# BatteryCharger.net
KiCad netlist of a schematic drawn in Altium Designer
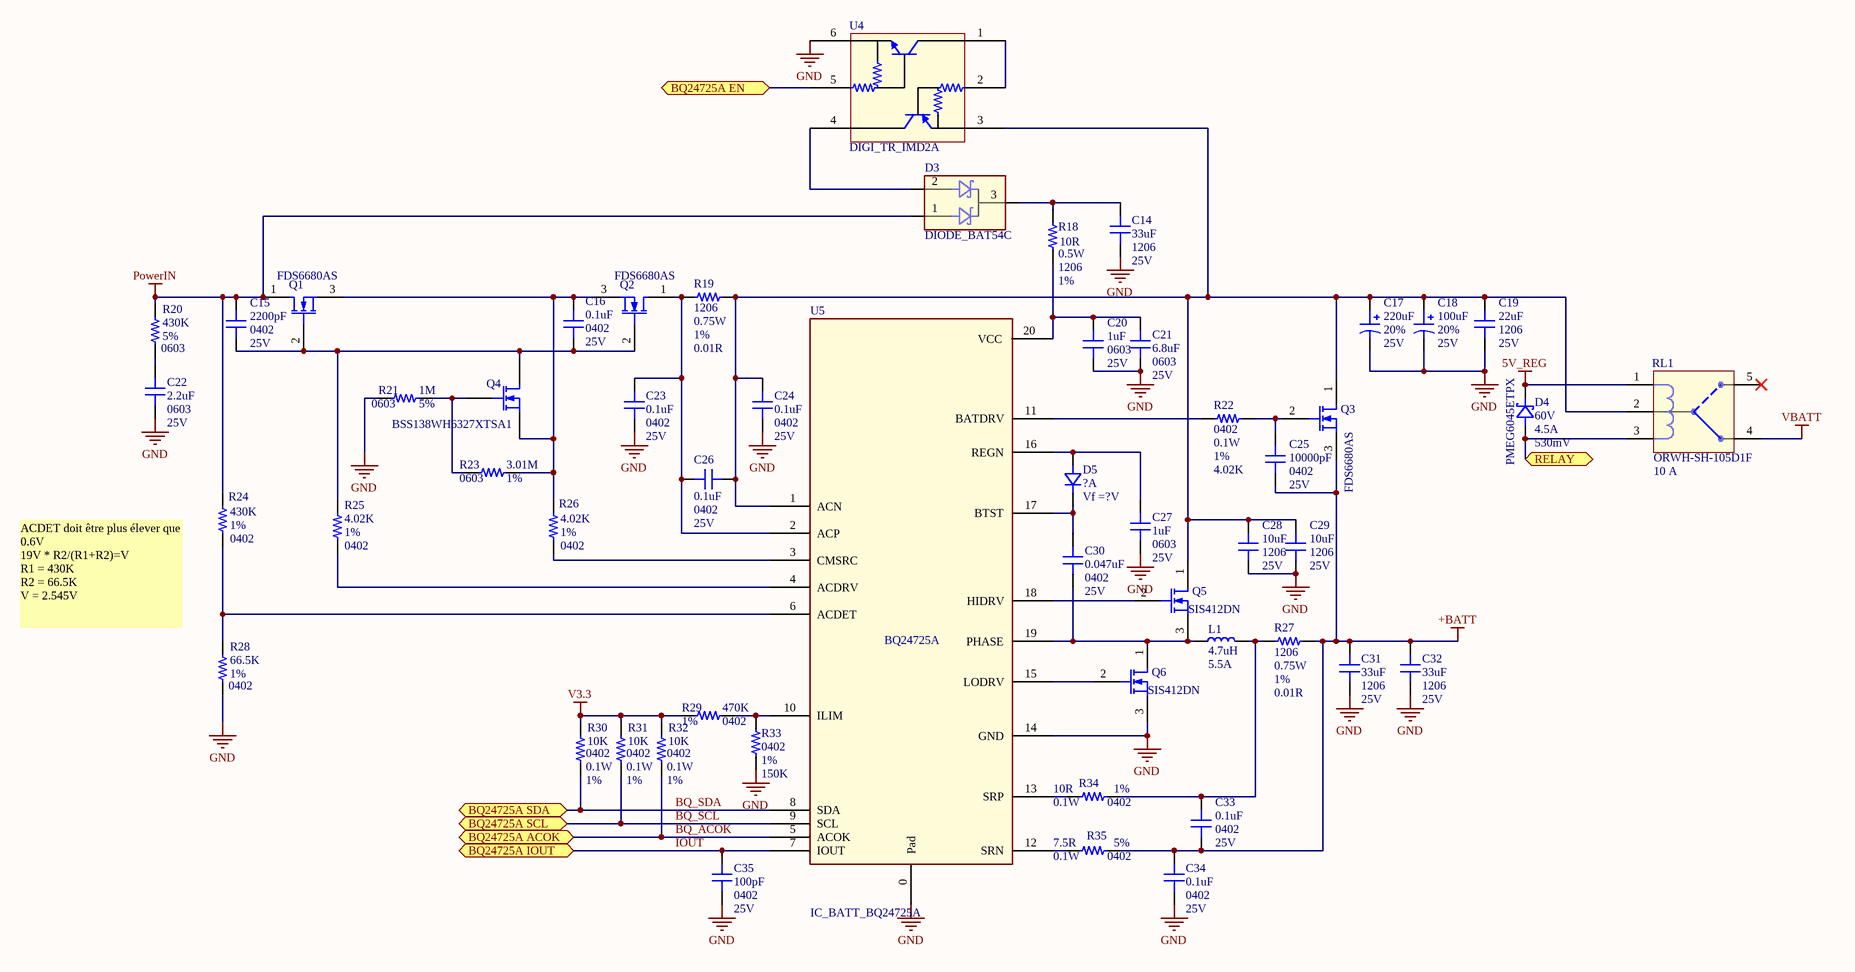
[diagram p0: BatteryCharger.SchDoc]

(export (version "E")
  (design (tool "Eeschema 10.0.6"))
  (components
    (comp (ref "C14")
      (value "33uF")
      (footprint "CAP_1206")
      (description "CAP CER 33uF 25V 1206")
      (fields
        (field (name "PART NUMBER") "C3216JB1E336M160AC‎")
        (field (name "PACKAGE") "1206")
        (field (name "VOLTAGE") "25V")
        (field (name "Comment") "CAP_‎C3216JB1E336M160AC‎")
      )
      (libsource (lib "SecureBot") (part "CAP_‎C3216JB1E336M160AC‎"))
    )
    (comp (ref "C15")
      (value "2200pF")
      (footprint "CAP_0402")
      (description "CAP CER 2200PF 25V 0402")
      (fields
        (field (name "PART NUMBER") "AC0402KRX7R8BB222‎")
        (field (name "PACKAGE") "0402")
        (field (name "VOLTAGE") "25V")
        (field (name "Comment") "CAP_AC0402KRX7R8BB222‎")
      )
      (libsource (lib "SecureBot") (part "CAP_AC0402KRX7R8BB222‎"))
    )
    (comp (ref "C16")
      (value "0.1uF")
      (footprint "CAP_0402")
      (description "CAP CER 0.1uF 25V 0402")
      (fields
        (field (name "PART NUMBER") "CL05A104KA5NNNC‎")
        (field (name "PACKAGE") "0402")
        (field (name "VOLTAGE") "25V")
        (field (name "Comment") "CAP_‎‎CL05A104KA5NNNC‎")
      )
      (libsource (lib "SecureBot") (part "CAP_‎‎CL05A104KA5NNNC‎"))
    )
    (comp (ref "C17")
      (value "220uF")
      (footprint "CAP UWT 8x10")
      (description "CAP ALU 220µF 25V")
      (fields
        (field (name "PART NUMBER") "UWT1E221MNL1GS")
        (field (name "TOLERANCE") "20%")
        (field (name "VOLTAGE") "25V")
        (field (name "Comment") "CAP_UWT1E221MNL1GS")
      )
      (libsource (lib "SecureBot") (part "CAP_UWT1E221MNL1GS"))
    )
    (comp (ref "C18")
      (value "100uF")
      (footprint "CAP ALU - 6.3mm DIA")
      (description "CAP ALU 100µF 25V")
      (fields
        (field (name "PART NUMBER") "UWT1E101MCL1GS")
        (field (name "TOLERANCE") "20%")
        (field (name "VOLTAGE") "25V")
        (field (name "Comment") "CAP_UWT1E101MCL1GS")
      )
      (libsource (lib "SecureBot") (part "CAP_UWT1E101MCL1GS"))
    )
    (comp (ref "C19")
      (value "22uF")
      (footprint "CAP_1206")
      (description "CAP CER 22uF 25V 1206")
      (fields
        (field (name "PART NUMBER") "CL31A226KAHNNNE‎")
        (field (name "PACKAGE") "1206")
        (field (name "VOLTAGE") "25V")
        (field (name "Comment") "CAP_‎‎CL31A226KAHNNNE‎")
      )
      (libsource (lib "SecureBot") (part "CAP_‎‎CL31A226KAHNNNE‎"))
    )
    (comp (ref "C20")
      (value "1uF")
      (footprint "CAP_0603")
      (description "CAP CER 1uF 25V 0603")
      (fields
        (field (name "PART NUMBER") "CL10A105KA8NNNC‎")
        (field (name "PACKAGE") "0603")
        (field (name "VOLTAGE") "25V")
        (field (name "Comment") "CAP_‎CL10A105KA8NNNC‎")
      )
      (libsource (lib "SecureBot") (part "CAP_‎CL10A105KA8NNNC‎"))
    )
    (comp (ref "C21")
      (value "6.8uF")
      (footprint "CAP_0603")
      (description "CAP CER 6.8uF 25V 0603")
      (fields
        (field (name "PART NUMBER") "C1608X5R1E685K080AC")
        (field (name "PACKAGE") "0603")
        (field (name "VOLTAGE") "25V")
        (field (name "Comment") "CAP_‎‎‎C1608X5R1E685K080AC")
      )
      (libsource (lib "SecureBot") (part "CAP_‎‎‎C1608X5R1E685K080AC"))
    )
    (comp (ref "C22")
      (value "2.2uF")
      (footprint "CAP_0603")
      (description "CAP CER 2.2uF 25V 0603")
      (fields
        (field (name "PART NUMBER") "GRM188R61E225KA12D‎")
        (field (name "PACKAGE") "0603")
        (field (name "VOLTAGE") "25V")
        (field (name "Comment") "CAP_‎‎GRM188R61E225KA12D‎")
      )
      (libsource (lib "SecureBot") (part "CAP_‎‎GRM188R61E225KA12D‎"))
    )
    (comp (ref "C23")
      (value "0.1uF")
      (footprint "CAP_0402")
      (description "CAP CER 0.1uF 25V 0402")
      (fields
        (field (name "PART NUMBER") "CL05A104KA5NNNC‎")
        (field (name "PACKAGE") "0402")
        (field (name "VOLTAGE") "25V")
        (field (name "Comment") "CAP_‎‎CL05A104KA5NNNC‎")
      )
      (libsource (lib "SecureBot") (part "CAP_‎‎CL05A104KA5NNNC‎"))
    )
    (comp (ref "C24")
      (value "0.1uF")
      (footprint "CAP_0402")
      (description "CAP CER 0.1uF 25V 0402")
      (fields
        (field (name "PART NUMBER") "CL05A104KA5NNNC‎")
        (field (name "PACKAGE") "0402")
        (field (name "VOLTAGE") "25V")
        (field (name "Comment") "CAP_‎‎CL05A104KA5NNNC‎")
      )
      (libsource (lib "SecureBot") (part "CAP_‎‎CL05A104KA5NNNC‎"))
    )
    (comp (ref "C25")
      (value "10000pF")
      (footprint "CAP_0402")
      (description "CAP CER 10000pF 25V 0402")
      (fields
        (field (name "PART NUMBER") "‎CL05B103KA5NNNC‎")
        (field (name "PACKAGE") "0402")
        (field (name "VOLTAGE") "25V")
        (field (name "Comment") "CAP_‎CL05B103KA5NNNC‎")
      )
      (libsource (lib "SecureBot") (part "CAP_‎CL05B103KA5NNNC‎"))
    )
    (comp (ref "C26")
      (value "0.1uF")
      (footprint "CAP_0402")
      (description "CAP CER 0.1uF 25V 0402")
      (fields
        (field (name "PART NUMBER") "CL05A104KA5NNNC‎")
        (field (name "PACKAGE") "0402")
        (field (name "VOLTAGE") "25V")
        (field (name "Comment") "CAP_‎‎CL05A104KA5NNNC‎")
      )
      (libsource (lib "SecureBot") (part "CAP_‎‎CL05A104KA5NNNC‎"))
    )
    (comp (ref "C27")
      (value "1uF")
      (footprint "CAP_0603")
      (description "CAP CER 1uF 25V 0603")
      (fields
        (field (name "PART NUMBER") "CL10A105KA8NNNC‎")
        (field (name "PACKAGE") "0603")
        (field (name "VOLTAGE") "25V")
        (field (name "Comment") "CAP_‎CL10A105KA8NNNC‎")
      )
      (libsource (lib "SecureBot") (part "CAP_‎CL10A105KA8NNNC‎"))
    )
    (comp (ref "C28")
      (value "10uF")
      (footprint "CAP_1206")
      (description "CAP CER 10uF 25V 1206")
      (fields
        (field (name "PART NUMBER") "CL31A106KAHNFNE‎")
        (field (name "PACKAGE") "1206")
        (field (name "VOLTAGE") "25V")
        (field (name "Comment") "CAP_‎CL31A106KAHNFNE‎")
      )
      (libsource (lib "SecureBot") (part "CAP_‎CL31A106KAHNFNE‎"))
    )
    (comp (ref "C29")
      (value "10uF")
      (footprint "CAP_1206")
      (description "CAP CER 10uF 25V 1206")
      (fields
        (field (name "PART NUMBER") "CL31A106KAHNFNE‎")
        (field (name "PACKAGE") "1206")
        (field (name "VOLTAGE") "25V")
        (field (name "Comment") "CAP_‎CL31A106KAHNFNE‎")
      )
      (libsource (lib "SecureBot") (part "CAP_‎CL31A106KAHNFNE‎"))
    )
    (comp (ref "C30")
      (value "0.047uF")
      (footprint "CAP_0402")
      (description "CAP CER 0.047uF 25V 0402")
      (fields
        (field (name "PART NUMBER") "‎C0402C473K3RACAUTO‎")
        (field (name "PACKAGE") "0402")
        (field (name "VOLTAGE") "25V")
        (field (name "Comment") "CAP_‎‎‎C0402C473K3RACAUTO‎")
      )
      (libsource (lib "SecureBot") (part "CAP_‎‎‎C0402C473K3RACAUTO‎"))
    )
    (comp (ref "C31")
      (value "33uF")
      (footprint "CAP_1206")
      (description "CAP CER 33uF 25V 1206")
      (fields
        (field (name "PART NUMBER") "C3216JB1E336M160AC‎")
        (field (name "PACKAGE") "1206")
        (field (name "VOLTAGE") "25V")
        (field (name "Comment") "CAP_‎C3216JB1E336M160AC‎")
      )
      (libsource (lib "SecureBot") (part "CAP_‎C3216JB1E336M160AC‎"))
    )
    (comp (ref "C32")
      (value "33uF")
      (footprint "CAP_1206")
      (description "CAP CER 33uF 25V 1206")
      (fields
        (field (name "PART NUMBER") "C3216JB1E336M160AC‎")
        (field (name "PACKAGE") "1206")
        (field (name "VOLTAGE") "25V")
        (field (name "Comment") "CAP_‎C3216JB1E336M160AC‎")
      )
      (libsource (lib "SecureBot") (part "CAP_‎C3216JB1E336M160AC‎"))
    )
    (comp (ref "C33")
      (value "0.1uF")
      (footprint "CAP_0402")
      (description "CAP CER 0.1uF 25V 0402")
      (fields
        (field (name "PART NUMBER") "CL05A104KA5NNNC‎")
        (field (name "PACKAGE") "0402")
        (field (name "VOLTAGE") "25V")
        (field (name "Comment") "CAP_‎‎CL05A104KA5NNNC‎")
      )
      (libsource (lib "SecureBot") (part "CAP_‎‎CL05A104KA5NNNC‎"))
    )
    (comp (ref "C34")
      (value "0.1uF")
      (footprint "CAP_0402")
      (description "CAP CER 0.1uF 25V 0402")
      (fields
        (field (name "PART NUMBER") "CL05A104KA5NNNC‎")
        (field (name "PACKAGE") "0402")
        (field (name "VOLTAGE") "25V")
        (field (name "Comment") "CAP_‎‎CL05A104KA5NNNC‎")
      )
      (libsource (lib "SecureBot") (part "CAP_‎‎CL05A104KA5NNNC‎"))
    )
    (comp (ref "C35")
      (value "100pF")
      (footprint "CAP_0402")
      (description "CAP CER 100pF 25V 0402")
      (fields
        (field (name "PART NUMBER") "CC0402KRX7R8BB101‎")
        (field (name "PACKAGE") "0402")
        (field (name "VOLTAGE") "25V")
        (field (name "Comment") "CAP_‎‎‎‎CC0402KRX7R8BB101‎")
      )
      (libsource (lib "SecureBot") (part "CAP_‎‎‎‎CC0402KRX7R8BB101‎"))
    )
    (comp (ref "D3")
      (value "DIODE_BAT54C")
      (footprint "BAT54C")
      (description "Dual input Diode")
      (fields (field (name "PART NUMBER") "BAT54C"))
      (libsource (lib "SecureBot") (part "DIODE_BAT54C"))
    )
    (comp (ref "D4")
      (value "DIODE_SCH_PMEG6045ETPX")
      (footprint "DO-214AC_SOD128")
      (description "Diode Schottky 60V 4.5A Surface Mount CFP5")
      (fields
        (field (name "VOLTAGE") "60V")
        (field (name "CURRENT") "4.5A")
        (field (name "VF") "530mV")
        (field (name "PART NUMBER") "PMEG6045ETPX")
      )
      (libsource (lib "SecureBot") (part "DIODE_SCH_PMEG6045ETPX"))
    )
    (comp (ref "D5")
      (value "DIODE BAT54")
      (footprint "BAT54")
      (fields
        (field (name "CURRENT") "?A")
        (field (name "VF") "Vf =?V")
        (field (name "PART NUMBER") "BAT54C")
      )
      (libsource (lib "SecureBot") (part "DIODE BAT54"))
    )
    (comp (ref "L1")
      (value "4.7uH")
      (footprint "ASPI-0630LR")
      (description "4.7µH Shielded Molded Inductor 5.5A 35mOhm")
      (fields
        (field (name "CURRENT") "5.5A")
        (field (name "PART NUMBER") "ASPI-0630LR")
        (field (name "Comment") "IND_ASPI-0630LR")
      )
      (libsource (lib "SecureBot") (part "IND_ASPI-0630LR"))
    )
    (comp (ref "Q1")
      (value "NMOS_FDS6680AS")
      (footprint "SO-8 FDS6680AS")
      (description "NMOS_N-Channel 30V 11.5A (Ta) 2.5W (Ta) Surface Mount 8-SOIC")
      (fields (field (name "PART NUMBER") "FDS6680AS"))
      (libsource (lib "SecureBot") (part "NMOS_FDS6680AS"))
    )
    (comp (ref "Q2")
      (value "NMOS_FDS6680AS")
      (footprint "SO-8 FDS6680AS")
      (description "NMOS_N-Channel 30V 11.5A (Ta) 2.5W (Ta) Surface Mount 8-SOIC")
      (fields (field (name "PART NUMBER") "FDS6680AS"))
      (libsource (lib "SecureBot") (part "NMOS_FDS6680AS"))
    )
    (comp (ref "Q3")
      (value "NMOS_FDS6680AS")
      (footprint "SO-8 FDS6680AS")
      (description "NMOS_N-Channel 30V 11.5A (Ta) 2.5W (Ta) Surface Mount 8-SOIC")
      (fields (field (name "PART NUMBER") "FDS6680AS"))
      (libsource (lib "SecureBot") (part "NMOS_FDS6680AS"))
    )
    (comp (ref "Q4")
      (value "MOSFET-N")
      (footprint "PG-SOT-323")
      (description "N-Channel MOSFET")
      (fields (field (name "PART NUMBER") "BSS138WH6327XTSA1") (field (name "PUBLISHER") "Altium Limited"))
      (libsource (lib "Miscellaneous Devices") (part "MOSFET-N"))
    )
    (comp (ref "Q5")
      (value "NMOS_SIS412DN")
      (footprint "SiS412DN")
      (description "NMOS_N-Channel 30V 12A (Tc) 3.2W (Ta), 15.6W (Tc)")
      (fields (field (name "PART NUMBER") "SIS412DN"))
      (libsource (lib "SecureBot") (part "NMOS_SIS412DN"))
    )
    (comp (ref "Q6")
      (value "NMOS_SIS412DN")
      (footprint "SiS412DN")
      (description "NMOS_N-Channel 30V 12A (Tc) 3.2W (Ta), 15.6W (Tc)")
      (fields (field (name "PART NUMBER") "SIS412DN"))
      (libsource (lib "SecureBot") (part "NMOS_SIS412DN"))
    )
    (comp (ref "R18")
      (value "10R")
      (footprint "RES_1206")
      (description "RES 10R 1% 1/2W 1206")
      (fields
        (field (name "PART NUMBER") "CRM1206-FX-10R0ELF‎")
        (field (name "POWER") "0.5W")
        (field (name "PACKAGE") "1206")
        (field (name "TOLERANCE") "1%")
        (field (name "Comment") "RES_CRM1206-FX-10R0ELF‎")
      )
      (libsource (lib "SecureBot") (part "RES_CRM1206-FX-10R0ELF‎"))
    )
    (comp (ref "R19")
      (value "0.01R")
      (footprint "RES_1206")
      (description "RES 0.01R 1% 3/4W 1206")
      (fields
        (field (name "PART NUMBER") "KRL1632E-M-R010-F-T5")
        (field (name "PACKAGE") "1206")
        (field (name "POWER") "0.75W")
        (field (name "TOLERANCE") "1%")
        (field (name "Comment") "RES_‎‎‎KRL1632E-M-R010-F-T5")
      )
      (libsource (lib "SecureBot") (part "RES_‎‎‎KRL1632E-M-R010-F-T5"))
    )
    (comp (ref "R20")
      (value "430K")
      (footprint "RES_0603")
      (description "RES 430K 5% 1/10W 0603")
      (fields
        (field (name "PART NUMBER") "RC0603JR-07430KL‎")
        (field (name "PACKAGE") "0603")
        (field (name "POWER") "0.1W")
        (field (name "TOLERANCE") "5%")
      )
      (libsource (lib "SecureBot") (part "RES_‎‎‎‎RC0603JR-07430KL‎"))
    )
    (comp (ref "R21")
      (value "1M")
      (footprint "RES_0603")
      (description "RES 1M 5% 1/10W 0603")
      (fields
        (field (name "PART NUMBER") "‎ERA-6AEB4020V‎")
        (field (name "PACKAGE") "0603")
        (field (name "POWER") "0.1W")
        (field (name "TOLERANCE") "5%")
      )
      (libsource (lib "SecureBot") (part "RES_‎‎‎ERA-6AEB4020V‎_1"))
    )
    (comp (ref "R22")
      (value "4.02K")
      (footprint "RES_0402")
      (description "RES 4.02K 1% 1/10W 0402")
      (fields
        (field (name "PART NUMBER") "ERJ-2RKF4021X‎")
        (field (name "PACKAGE") "0402")
        (field (name "POWER") "0.1W")
        (field (name "TOLERANCE") "1%")
        (field (name "Comment") "RES_‎‎‎ERJ-2RKF4021X‎")
      )
      (libsource (lib "SecureBot") (part "RES_‎‎‎ERJ-2RKF4021X‎"))
    )
    (comp (ref "R23")
      (value "3.01M")
      (footprint "RES_0603")
      (description "RES 3.01M 1% 1/10W 0603")
      (fields
        (field (name "PART NUMBER") "RC0603FR-073M01L‎")
        (field (name "PACKAGE") "0603")
        (field (name "POWER") "0.1W")
        (field (name "TOLERANCE") "1%")
      )
      (libsource (lib "SecureBot") (part "RES_‎‎‎‎RC0603FR-073M01L‎"))
    )
    (comp (ref "R24")
      (value "430K")
      (footprint "RES_0402")
      (description "RES 430K 1% 1/16W 0402")
      (fields
        (field (name "PART NUMBER") "RC0402FR-07430KL‎")
        (field (name "PACKAGE") "0402")
        (field (name "POWER") "0.0625W")
        (field (name "TOLERANCE") "1%")
      )
      (libsource (lib "SecureBot") (part "RES_RC0402FR-07430KL‎"))
    )
    (comp (ref "R25")
      (value "4.02K")
      (footprint "RES_0402")
      (description "RES 4.02K 1% 1/10W 0402")
      (fields
        (field (name "PART NUMBER") "ERJ-2RKF4021X‎")
        (field (name "PACKAGE") "0402")
        (field (name "POWER") "0.1W")
        (field (name "TOLERANCE") "1%")
      )
      (libsource (lib "SecureBot") (part "RES_‎‎‎ERJ-2RKF4021X‎"))
    )
    (comp (ref "R26")
      (value "4.02K")
      (footprint "RES_0402")
      (description "RES 4.02K 1% 1/10W 0402")
      (fields
        (field (name "PART NUMBER") "ERJ-2RKF4021X‎")
        (field (name "PACKAGE") "0402")
        (field (name "POWER") "0.1W")
        (field (name "TOLERANCE") "1%")
      )
      (libsource (lib "SecureBot") (part "RES_‎‎‎ERJ-2RKF4021X‎"))
    )
    (comp (ref "R27")
      (value "0.01R")
      (footprint "RES_1206")
      (description "RES 0.01R 1% 3/4W 1206")
      (fields
        (field (name "PART NUMBER") "KRL1632E-M-R010-F-T5")
        (field (name "PACKAGE") "1206")
        (field (name "POWER") "0.75W")
        (field (name "TOLERANCE") "1%")
        (field (name "Comment") "RES_‎‎‎KRL1632E-M-R010-F-T5")
      )
      (libsource (lib "SecureBot") (part "RES_‎‎‎KRL1632E-M-R010-F-T5"))
    )
    (comp (ref "R28")
      (value "66.5K")
      (footprint "RES_0402")
      (description "RES 66.5K 1% 1/16W 0402")
      (fields
        (field (name "PART NUMBER") "RMCF0402FT66K5")
        (field (name "PACKAGE") "0402")
        (field (name "POWER") "0.0625W")
        (field (name "TOLERANCE") "1%")
      )
      (libsource (lib "SecureBot") (part "RES_‎‎‎‎RMCF0402FT66K5"))
    )
    (comp (ref "R29")
      (value "470K")
      (footprint "RES_0402")
      (description "RES 470K 1% 1/10W 0402")
      (fields
        (field (name "PART NUMBER") "MCS04020C4703FE000‎")
        (field (name "PACKAGE") "0402")
        (field (name "POWER") "0.1W")
        (field (name "TOLERANCE") "1%")
      )
      (libsource (lib "SecureBot") (part "RES_MCS04020C4703FE000‎"))
    )
    (comp (ref "R30")
      (value "10K")
      (footprint "RES_0402")
      (description "RES 10K 1% 1/10W 0402")
      (fields
        (field (name "PART NUMBER") "‎MCS0402MC1002FE000‎")
        (field (name "PACKAGE") "0402")
        (field (name "POWER") "0.1W")
        (field (name "TOLERANCE") "1%")
        (field (name "Comment") "RES_‎MCS0402MC1002FE000‎")
      )
      (libsource (lib "SecureBot") (part "RES_‎MCS0402MC1002FE000‎"))
    )
    (comp (ref "R31")
      (value "10K")
      (footprint "RES_0402")
      (description "RES 10K 1% 1/10W 0402")
      (fields
        (field (name "PART NUMBER") "‎MCS0402MC1002FE000‎")
        (field (name "PACKAGE") "0402")
        (field (name "POWER") "0.1W")
        (field (name "TOLERANCE") "1%")
        (field (name "Comment") "RES_‎MCS0402MC1002FE000‎")
      )
      (libsource (lib "SecureBot") (part "RES_‎MCS0402MC1002FE000‎"))
    )
    (comp (ref "R32")
      (value "10K")
      (footprint "RES_0402")
      (description "RES 10K 1% 1/10W 0402")
      (fields
        (field (name "PART NUMBER") "‎MCS0402MC1002FE000‎")
        (field (name "PACKAGE") "0402")
        (field (name "POWER") "0.1W")
        (field (name "TOLERANCE") "1%")
        (field (name "Comment") "RES_‎MCS0402MC1002FE000‎")
      )
      (libsource (lib "SecureBot") (part "RES_‎MCS0402MC1002FE000‎"))
    )
    (comp (ref "R33")
      (value "150K")
      (footprint "RES_0402")
      (description "RES 150K 1% 1/10W 0402")
      (fields
        (field (name "PART NUMBER") "MCS04020C1503FE000‎")
        (field (name "PACKAGE") "0402")
        (field (name "POWER") "0.1W")
        (field (name "TOLERANCE") "1%")
      )
      (libsource (lib "SecureBot") (part "RES_‎‎‎MCS04020C1503FE000‎"))
    )
    (comp (ref "R34")
      (value "10R")
      (footprint "RES_0402")
      (description "RES 10R 1% 1/10W 0402")
      (fields
        (field (name "PART NUMBER") "ERJ-2RKF10R0X‎")
        (field (name "POWER") "0.1W")
        (field (name "TOLERANCE") "1%")
        (field (name "PACKAGE") "0402")
        (field (name "Comment") "RES_ERJ-2RKF10R0X‎")
      )
      (libsource (lib "SecureBot") (part "RES_ERJ-2RKF10R0X‎"))
    )
    (comp (ref "R35")
      (value "7.5R")
      (footprint "RES_0402")
      (description "RES 7.5R 5% 1/10W 0402")
      (fields
        (field (name "PART NUMBER") "ERJ-2GEJ7R5X‎")
        (field (name "PACKAGE") "0402")
        (field (name "POWER") "0.1W")
        (field (name "TOLERANCE") "5%")
        (field (name "Comment") "RES_‎‎‎ERJ-2GEJ7R5X‎")
      )
      (libsource (lib "SecureBot") (part "RES_‎‎‎ERJ-2GEJ7R5X‎"))
    )
    (comp (ref "RL1")
      (value "Relay SPDT")
      (footprint "ORWH-SH")
      (fields (field (name "PART NUMBER") "ORWH-SH-105D1F") (field (name "A MAX") "10 A"))
      (libsource (lib "SecureBot") (part "Relay SPDT"))
    )
    (comp (ref "U4")
      (value "DIGI_TR_IMD2A")
      (footprint "IMD2A")
      (description "Dual digital Transistor")
      (fields (field (name "PART NUMBER") "IMD2A"))
      (libsource (lib "SecureBot") (part "DIGI_TR_IMD2A"))
    )
    (comp (ref "U5")
      (value "IC_BATT_BQ24725A")
      (footprint "bq24725A")
      (description "Battery Charger")
      (fields (field (name "PART NUMBER") "BQ24725A"))
      (libsource (lib "SecureBot") (part "IC_BATT_BQ24725A"))
    )
  )
  (nets
    (net (code "1") (name "+BATT") (class "Default")
      (node (ref "C25") (pin "2") (pinfunction "2_2") (pintype "passive"))
      (node (ref "C31") (pin "1") (pinfunction "1_1") (pintype "passive"))
      (node (ref "C32") (pin "1") (pinfunction "1_1") (pintype "passive"))
      (node (ref "C33") (pin "2") (pinfunction "2_2") (pintype "passive"))
      (node (ref "C34") (pin "1") (pinfunction "1_1") (pintype "passive"))
      (node (ref "Q3") (pin "3") (pinfunction "S_3") (pintype "passive"))
      (node (ref "R27") (pin "2") (pinfunction "2_2") (pintype "passive"))
      (node (ref "R35") (pin "2") (pinfunction "2_2") (pintype "passive"))
    )
    (net (code "2") (name "/BQ24725A EN") (class "Default")
      (node (ref "U4") (pin "5") (pinfunction "5_5") (pintype "passive"))
    )
    (net (code "3") (name "/BQ_ACOK") (class "Default")
      (node (ref "R32") (pin "2") (pinfunction "2_2") (pintype "passive"))
      (node (ref "U5") (pin "5") (pinfunction "ACOK_5") (pintype "passive"))
    )
    (net (code "4") (name "/BQ_SCL") (class "Default")
      (node (ref "R31") (pin "2") (pinfunction "2_2") (pintype "passive"))
      (node (ref "U5") (pin "9") (pinfunction "SCL_9") (pintype "passive"))
    )
    (net (code "5") (name "/BQ_SDA") (class "Default")
      (node (ref "R30") (pin "2") (pinfunction "2_2") (pintype "passive"))
      (node (ref "U5") (pin "8") (pinfunction "SDA_8") (pintype "passive"))
    )
    (net (code "6") (name "/IOUT") (class "Default")
      (node (ref "C35") (pin "1") (pinfunction "1_1") (pintype "passive"))
      (node (ref "U5") (pin "7") (pinfunction "IOUT_7") (pintype "passive"))
    )
    (net (code "7") (name "/RELAY") (class "Default")
      (node (ref "D4") (pin "1") (pinfunction "1_1") (pintype "passive"))
      (node (ref "RL1") (pin "3") (pinfunction "3_3") (pintype "passive"))
    )
    (net (code "8") (name "5V_REG") (class "Default")
      (node (ref "D4") (pin "2") (pinfunction "2_2") (pintype "passive"))
      (node (ref "RL1") (pin "1") (pinfunction "1_1") (pintype "passive"))
    )
    (net (code "9") (name "GND") (class "Default")
      (node (ref "C14") (pin "2") (pinfunction "2_2") (pintype "passive"))
      (node (ref "C17") (pin "2") (pinfunction "2_2") (pintype "passive"))
      (node (ref "C18") (pin "2") (pinfunction "2_2") (pintype "passive"))
      (node (ref "C19") (pin "2") (pinfunction "2_2") (pintype "passive"))
      (node (ref "C20") (pin "2") (pinfunction "2_2") (pintype "passive"))
      (node (ref "C21") (pin "2") (pinfunction "2_2") (pintype "passive"))
      (node (ref "C22") (pin "2") (pinfunction "2_2") (pintype "passive"))
      (node (ref "C23") (pin "2") (pinfunction "2_2") (pintype "passive"))
      (node (ref "C24") (pin "2") (pinfunction "2_2") (pintype "passive"))
      (node (ref "C27") (pin "2") (pinfunction "2_2") (pintype "passive"))
      (node (ref "C28") (pin "2") (pinfunction "2_2") (pintype "passive"))
      (node (ref "C29") (pin "2") (pinfunction "2_2") (pintype "passive"))
      (node (ref "C31") (pin "2") (pinfunction "2_2") (pintype "passive"))
      (node (ref "C32") (pin "2") (pinfunction "2_2") (pintype "passive"))
      (node (ref "C34") (pin "2") (pinfunction "2_2") (pintype "passive"))
      (node (ref "C35") (pin "2") (pinfunction "2_2") (pintype "passive"))
      (node (ref "Q6") (pin "3") (pinfunction "S_3") (pintype "passive"))
      (node (ref "R21") (pin "1") (pinfunction "1_1") (pintype "passive"))
      (node (ref "R28") (pin "2") (pinfunction "2_2") (pintype "passive"))
      (node (ref "R33") (pin "1") (pinfunction "1_1") (pintype "passive"))
      (node (ref "U4") (pin "6") (pinfunction "6_6") (pintype "passive"))
      (node (ref "U5") (pin "0") (pinfunction "Pad_0") (pintype "passive"))
      (node (ref "U5") (pin "14") (pinfunction "GND_14") (pintype "passive"))
    )
    (net (code "10") (name "Net-(C14-Pad1)") (class "Default")
      (node (ref "C14") (pin "1") (pinfunction "1_1") (pintype "passive"))
      (node (ref "D3") (pin "3") (pinfunction "3_3") (pintype "passive"))
      (node (ref "R18") (pin "1") (pinfunction "1_1") (pintype "passive"))
    )
    (net (code "11") (name "Net-(C22-Pad1)") (class "Default")
      (node (ref "C22") (pin "1") (pinfunction "1_1") (pintype "passive"))
      (node (ref "R20") (pin "2") (pinfunction "2_2") (pintype "passive"))
    )
    (net (code "12") (name "Net-(C33-Pad1)") (class "Default")
      (node (ref "C33") (pin "1") (pinfunction "1_1") (pintype "passive"))
      (node (ref "L1") (pin "2") (pinfunction "2_2") (pintype "passive"))
      (node (ref "R27") (pin "1") (pinfunction "1_1") (pintype "passive"))
      (node (ref "R34") (pin "2") (pinfunction "2_2") (pintype "passive"))
    )
    (net (code "13") (name "Net-(D3-Pad2)") (class "Default")
      (node (ref "D3") (pin "2") (pinfunction "2_2") (pintype "passive"))
      (node (ref "U4") (pin "4") (pinfunction "4_4") (pintype "passive"))
    )
    (net (code "14") (name "Net-(Q1-G)") (class "Default")
      (node (ref "C15") (pin "2") (pinfunction "2_2") (pintype "passive"))
      (node (ref "C16") (pin "2") (pinfunction "2_2") (pintype "passive"))
      (node (ref "Q1") (pin "2") (pinfunction "G_2") (pintype "passive"))
      (node (ref "Q2") (pin "2") (pinfunction "G_2") (pintype "passive"))
      (node (ref "Q4") (pin "3") (pinfunction "D_3") (pintype "passive"))
      (node (ref "R25") (pin "1") (pinfunction "1_1") (pintype "passive"))
    )
    (net (code "15") (name "Net-(Q1-S)") (class "Default")
      (node (ref "C16") (pin "1") (pinfunction "1_1") (pintype "passive"))
      (node (ref "Q1") (pin "3") (pinfunction "S_3") (pintype "passive"))
      (node (ref "Q2") (pin "3") (pinfunction "S_3") (pintype "passive"))
      (node (ref "Q4") (pin "2") (pinfunction "S_2") (pintype "passive"))
      (node (ref "R23") (pin "2") (pinfunction "2_2") (pintype "passive"))
      (node (ref "R26") (pin "1") (pinfunction "1_1") (pintype "passive"))
    )
    (net (code "16") (name "Net-(Q2-D)") (class "Default")
      (node (ref "C23") (pin "1") (pinfunction "1_1") (pintype "passive"))
      (node (ref "C26") (pin "1") (pinfunction "1_1") (pintype "passive"))
      (node (ref "Q2") (pin "1") (pinfunction "D_1") (pintype "passive"))
      (node (ref "R19") (pin "1") (pinfunction "1_1") (pintype "passive"))
      (node (ref "U5") (pin "2") (pinfunction "ACP_2") (pintype "passive"))
    )
    (net (code "17") (name "Net-(Q3-D)") (class "Default")
      (node (ref "C17") (pin "1") (pinfunction "1_1") (pintype "passive"))
      (node (ref "C18") (pin "1") (pinfunction "1_1") (pintype "passive"))
      (node (ref "C19") (pin "1") (pinfunction "1_1") (pintype "passive"))
      (node (ref "C24") (pin "1") (pinfunction "1_1") (pintype "passive"))
      (node (ref "C26") (pin "2") (pinfunction "2_2") (pintype "passive"))
      (node (ref "C28") (pin "1") (pinfunction "1_1") (pintype "passive"))
      (node (ref "C29") (pin "1") (pinfunction "1_1") (pintype "passive"))
      (node (ref "Q3") (pin "1") (pinfunction "D_1") (pintype "passive"))
      (node (ref "Q5") (pin "1") (pinfunction "D_1") (pintype "passive"))
      (node (ref "R19") (pin "2") (pinfunction "2_2") (pintype "passive"))
      (node (ref "RL1") (pin "2") (pinfunction "2_2") (pintype "passive"))
      (node (ref "U4") (pin "3") (pinfunction "3_3") (pintype "passive"))
      (node (ref "U5") (pin "1") (pinfunction "ACN_1") (pintype "passive"))
    )
    (net (code "18") (name "Net-(Q3-G)") (class "Default")
      (node (ref "C25") (pin "1") (pinfunction "1_1") (pintype "passive"))
      (node (ref "Q3") (pin "2") (pinfunction "G_2") (pintype "passive"))
      (node (ref "R22") (pin "2") (pinfunction "2_2") (pintype "passive"))
    )
    (net (code "19") (name "Net-(Q4-G)") (class "Default")
      (node (ref "Q4") (pin "1") (pinfunction "G_1") (pintype "passive"))
      (node (ref "R21") (pin "2") (pinfunction "2_2") (pintype "passive"))
      (node (ref "R23") (pin "1") (pinfunction "1_1") (pintype "passive"))
    )
    (net (code "20") (name "Net-(Q5-G)") (class "Default")
      (node (ref "Q5") (pin "2") (pinfunction "G_2") (pintype "passive"))
      (node (ref "U5") (pin "18") (pinfunction "HIDRV_18") (pintype "passive"))
    )
    (net (code "21") (name "Net-(Q5-S)") (class "Default")
      (node (ref "C30") (pin "2") (pinfunction "2_2") (pintype "passive"))
      (node (ref "L1") (pin "1") (pinfunction "1_1") (pintype "passive"))
      (node (ref "Q5") (pin "3") (pinfunction "S_3") (pintype "passive"))
      (node (ref "Q6") (pin "1") (pinfunction "D_1") (pintype "passive"))
      (node (ref "U5") (pin "19") (pinfunction "PHASE_19") (pintype "passive"))
    )
    (net (code "22") (name "Net-(Q6-G)") (class "Default")
      (node (ref "Q6") (pin "2") (pinfunction "G_2") (pintype "passive"))
      (node (ref "U5") (pin "15") (pinfunction "LODRV_15") (pintype "passive"))
    )
    (net (code "23") (name "Net-(U4-Pad1)") (class "Default")
      (node (ref "U4") (pin "1") (pinfunction "1_1") (pintype "passive"))
      (node (ref "U4") (pin "2") (pinfunction "2_2") (pintype "passive"))
    )
    (net (code "24") (name "Net-(U5-ACDET)") (class "Default")
      (node (ref "R24") (pin "2") (pinfunction "2_2") (pintype "passive"))
      (node (ref "R28") (pin "1") (pinfunction "1_1") (pintype "passive"))
      (node (ref "U5") (pin "6") (pinfunction "ACDET_6") (pintype "passive"))
    )
    (net (code "25") (name "Net-(U5-ACDRV)") (class "Default")
      (node (ref "R25") (pin "2") (pinfunction "2_2") (pintype "passive"))
      (node (ref "U5") (pin "4") (pinfunction "ACDRV_4") (pintype "passive"))
    )
    (net (code "26") (name "Net-(U5-BATDRV)") (class "Default")
      (node (ref "R22") (pin "1") (pinfunction "1_1") (pintype "passive"))
      (node (ref "U5") (pin "11") (pinfunction "BATDRV_11") (pintype "passive"))
    )
    (net (code "27") (name "Net-(U5-BTST)") (class "Default")
      (node (ref "C30") (pin "1") (pinfunction "1_1") (pintype "passive"))
      (node (ref "D5") (pin "3") (pinfunction "3_3") (pintype "passive"))
      (node (ref "U5") (pin "17") (pinfunction "BTST_17") (pintype "passive"))
    )
    (net (code "28") (name "Net-(U5-CMSRC)") (class "Default")
      (node (ref "R26") (pin "2") (pinfunction "2_2") (pintype "passive"))
      (node (ref "U5") (pin "3") (pinfunction "CMSRC_3") (pintype "passive"))
    )
    (net (code "29") (name "Net-(U5-ILIM)") (class "Default")
      (node (ref "R29") (pin "2") (pinfunction "2_2") (pintype "passive"))
      (node (ref "R33") (pin "2") (pinfunction "2_2") (pintype "passive"))
      (node (ref "U5") (pin "10") (pinfunction "ILIM_10") (pintype "passive"))
    )
    (net (code "30") (name "Net-(U5-REGN)") (class "Default")
      (node (ref "C27") (pin "1") (pinfunction "1_1") (pintype "passive"))
      (node (ref "D5") (pin "1") (pinfunction "1_1") (pintype "passive"))
      (node (ref "U5") (pin "16") (pinfunction "REGN_16") (pintype "passive"))
    )
    (net (code "31") (name "Net-(U5-SRN)") (class "Default")
      (node (ref "R35") (pin "1") (pinfunction "1_1") (pintype "passive"))
      (node (ref "U5") (pin "12") (pinfunction "SRN_12") (pintype "passive"))
    )
    (net (code "32") (name "Net-(U5-SRP)") (class "Default")
      (node (ref "R34") (pin "1") (pinfunction "1_1") (pintype "passive"))
      (node (ref "U5") (pin "13") (pinfunction "SRP_13") (pintype "passive"))
    )
    (net (code "33") (name "Net-(U5-VCC)") (class "Default")
      (node (ref "C20") (pin "1") (pinfunction "1_1") (pintype "passive"))
      (node (ref "C21") (pin "1") (pinfunction "1_1") (pintype "passive"))
      (node (ref "R18") (pin "2") (pinfunction "2_2") (pintype "passive"))
      (node (ref "U5") (pin "20") (pinfunction "VCC_20") (pintype "passive"))
    )
    (net (code "34") (name "PowerIN") (class "Default")
      (node (ref "C15") (pin "1") (pinfunction "1_1") (pintype "passive"))
      (node (ref "D3") (pin "1") (pinfunction "1_1") (pintype "passive"))
      (node (ref "Q1") (pin "1") (pinfunction "D_1") (pintype "passive"))
      (node (ref "R20") (pin "1") (pinfunction "1_1") (pintype "passive"))
      (node (ref "R24") (pin "1") (pinfunction "1_1") (pintype "passive"))
    )
    (net (code "35") (name "V3.3") (class "Default")
      (node (ref "R29") (pin "1") (pinfunction "1_1") (pintype "passive"))
      (node (ref "R30") (pin "1") (pinfunction "1_1") (pintype "passive"))
      (node (ref "R31") (pin "1") (pinfunction "1_1") (pintype "passive"))
      (node (ref "R32") (pin "1") (pinfunction "1_1") (pintype "passive"))
    )
    (net (code "36") (name "VBATT") (class "Default")
      (node (ref "RL1") (pin "4") (pinfunction "4_4") (pintype "passive"))
    )
    (net (code "37") (name "unconnected-(RL1-Pad5)") (class "Default")
      (node (ref "RL1") (pin "5") (pinfunction "5_5") (pintype "passive+no_connect"))
    )
  )
)
